# Wheel_Test_Signal.net
KiCad netlist of a schematic drawn in EAGLE
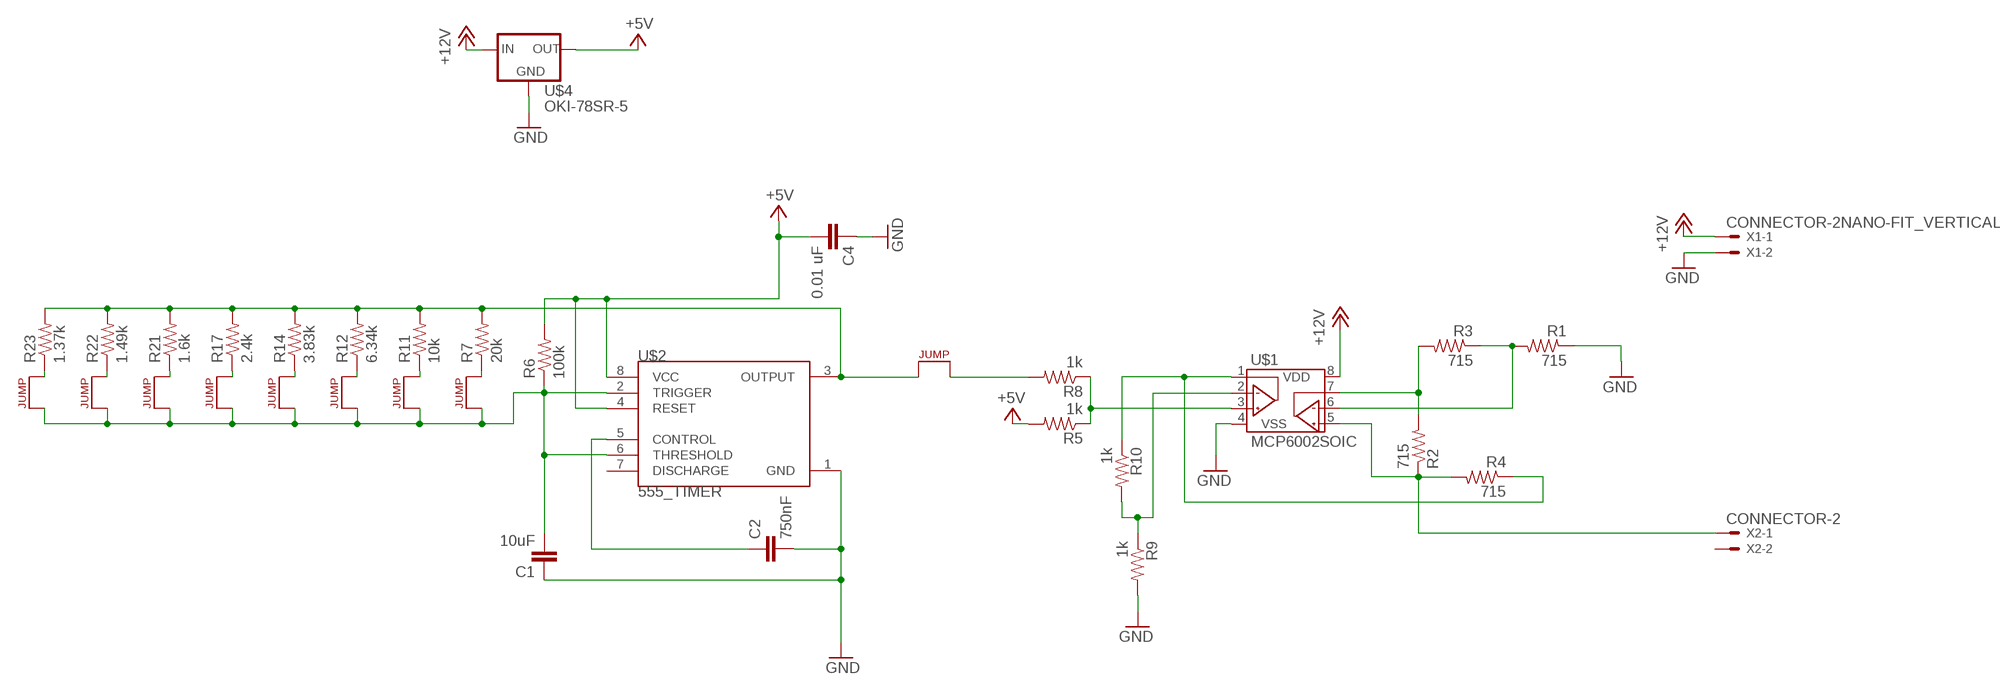
[diagram p0: schematic, sheet 1, part 1 of 2]
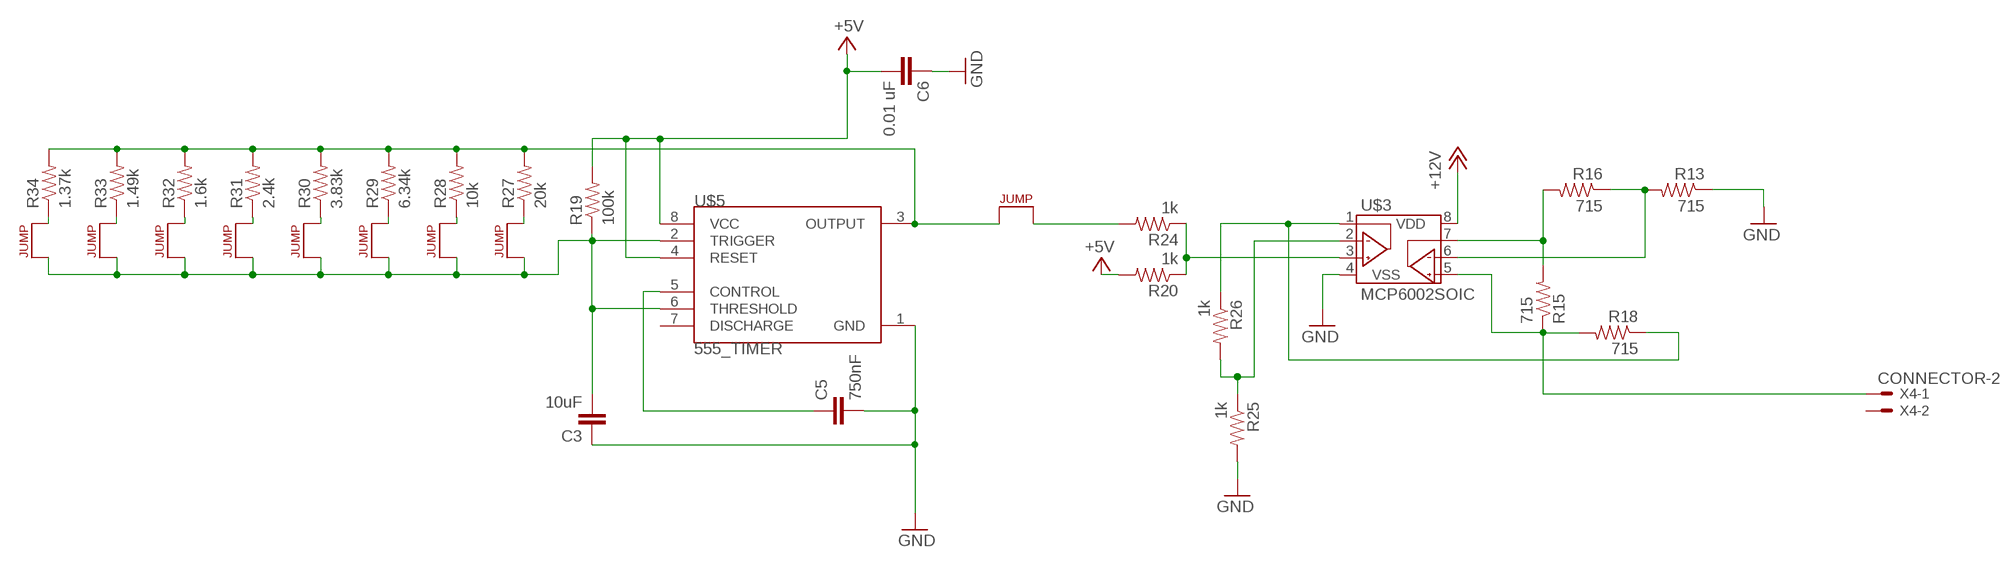
[diagram p1: schematic, sheet 1, part 2 of 2]

(export (version "E")
  (design (tool "Eeschema 10.0.6"))
  (components
    (comp (ref "C1")
      (value "10uF")
      (footprint "eagle-import:0603-CAP")
      (libsource (lib "eagle-import") (part "CAP0603-CAP"))
    )
    (comp (ref "C2")
      (value "750nF")
      (footprint "eagle-import:0603-CAP")
      (libsource (lib "eagle-import") (part "CAP0603-CAP"))
    )
    (comp (ref "C3")
      (value "10uF")
      (footprint "eagle-import:0603-CAP")
      (libsource (lib "eagle-import") (part "CAP0603-CAP"))
    )
    (comp (ref "C4")
      (value "0.01 uF")
      (footprint "eagle-import:0603-CAP")
      (libsource (lib "eagle-import") (part "CAP0603-CAP"))
    )
    (comp (ref "C5")
      (value "750nF")
      (footprint "eagle-import:0603-CAP")
      (libsource (lib "eagle-import") (part "CAP0603-CAP"))
    )
    (comp (ref "C6")
      (value "0.01 uF")
      (footprint "eagle-import:0603-CAP")
      (libsource (lib "eagle-import") (part "CAP0603-CAP"))
    )
    (comp (ref "J1")
      (value "JUMPER.1")
      (footprint "eagle-import:1X02")
      (libsource (lib "eagle-import") (part "JUMPER.1"))
    )
    (comp (ref "J2")
      (value "JUMPER.1")
      (footprint "eagle-import:1X02")
      (libsource (lib "eagle-import") (part "JUMPER.1"))
    )
    (comp (ref "J3")
      (value "JUMPER.1")
      (footprint "eagle-import:1X02")
      (libsource (lib "eagle-import") (part "JUMPER.1"))
    )
    (comp (ref "J4")
      (value "JUMPER.1")
      (footprint "eagle-import:1X02")
      (libsource (lib "eagle-import") (part "JUMPER.1"))
    )
    (comp (ref "J5")
      (value "JUMPER.1")
      (footprint "eagle-import:1X02")
      (libsource (lib "eagle-import") (part "JUMPER.1"))
    )
    (comp (ref "J6")
      (value "JUMPER.1")
      (footprint "eagle-import:1X02")
      (libsource (lib "eagle-import") (part "JUMPER.1"))
    )
    (comp (ref "J7")
      (value "JUMPER.1")
      (footprint "eagle-import:1X02")
      (libsource (lib "eagle-import") (part "JUMPER.1"))
    )
    (comp (ref "J8")
      (value "JUMPER.1")
      (footprint "eagle-import:1X02")
      (libsource (lib "eagle-import") (part "JUMPER.1"))
    )
    (comp (ref "J9")
      (value "JUMPER.1")
      (footprint "eagle-import:1X02")
      (libsource (lib "eagle-import") (part "JUMPER.1"))
    )
    (comp (ref "J10")
      (value "JUMPER.1")
      (footprint "eagle-import:1X02")
      (libsource (lib "eagle-import") (part "JUMPER.1"))
    )
    (comp (ref "J11")
      (value "JUMPER.1")
      (footprint "eagle-import:1X02")
      (libsource (lib "eagle-import") (part "JUMPER.1"))
    )
    (comp (ref "J12")
      (value "JUMPER.1")
      (footprint "eagle-import:1X02")
      (libsource (lib "eagle-import") (part "JUMPER.1"))
    )
    (comp (ref "J13")
      (value "JUMPER.1")
      (footprint "eagle-import:1X02")
      (libsource (lib "eagle-import") (part "JUMPER.1"))
    )
    (comp (ref "J14")
      (value "JUMPER.1")
      (footprint "eagle-import:1X02")
      (libsource (lib "eagle-import") (part "JUMPER.1"))
    )
    (comp (ref "J15")
      (value "JUMPER.1")
      (footprint "eagle-import:1X02")
      (libsource (lib "eagle-import") (part "JUMPER.1"))
    )
    (comp (ref "J16")
      (value "JUMPER.1")
      (footprint "eagle-import:1X02")
      (libsource (lib "eagle-import") (part "JUMPER.1"))
    )
    (comp (ref "J17")
      (value "JUMPER.1")
      (footprint "eagle-import:1X02")
      (libsource (lib "eagle-import") (part "JUMPER.1"))
    )
    (comp (ref "J18")
      (value "JUMPER.1")
      (footprint "eagle-import:1X02")
      (libsource (lib "eagle-import") (part "JUMPER.1"))
    )
    (comp (ref "R1")
      (value "715")
      (footprint "eagle-import:0603-RES")
      (libsource (lib "eagle-import") (part "RESISTOR0603"))
    )
    (comp (ref "R2")
      (value "715")
      (footprint "eagle-import:0603-RES")
      (libsource (lib "eagle-import") (part "RESISTOR0603"))
    )
    (comp (ref "R3")
      (value "715")
      (footprint "eagle-import:0603-RES")
      (libsource (lib "eagle-import") (part "RESISTOR0603"))
    )
    (comp (ref "R4")
      (value "715")
      (footprint "eagle-import:0603-RES")
      (libsource (lib "eagle-import") (part "RESISTOR0603"))
    )
    (comp (ref "R5")
      (value "1k")
      (footprint "eagle-import:0603-RES")
      (libsource (lib "eagle-import") (part "RESISTOR0603"))
    )
    (comp (ref "R6")
      (value "100k")
      (footprint "eagle-import:0603-RES")
      (libsource (lib "eagle-import") (part "RESISTOR0603"))
    )
    (comp (ref "R7")
      (value "20k")
      (footprint "eagle-import:0603-RES")
      (libsource (lib "eagle-import") (part "RESISTOR0603"))
    )
    (comp (ref "R8")
      (value "1k")
      (footprint "eagle-import:0603-RES")
      (libsource (lib "eagle-import") (part "RESISTOR0603"))
    )
    (comp (ref "R9")
      (value "1k")
      (footprint "eagle-import:0603-RES")
      (libsource (lib "eagle-import") (part "RESISTOR0603"))
    )
    (comp (ref "R10")
      (value "1k")
      (footprint "eagle-import:0603-RES")
      (libsource (lib "eagle-import") (part "RESISTOR0603"))
    )
    (comp (ref "R11")
      (value "10k")
      (footprint "eagle-import:0603-RES")
      (libsource (lib "eagle-import") (part "RESISTOR0603"))
    )
    (comp (ref "R12")
      (value "6.34k")
      (footprint "eagle-import:0603-RES")
      (libsource (lib "eagle-import") (part "RESISTOR0603"))
    )
    (comp (ref "R13")
      (value "715")
      (footprint "eagle-import:0603-RES")
      (libsource (lib "eagle-import") (part "RESISTOR0603"))
    )
    (comp (ref "R14")
      (value "3.83k")
      (footprint "eagle-import:0603-RES")
      (libsource (lib "eagle-import") (part "RESISTOR0603"))
    )
    (comp (ref "R15")
      (value "715")
      (footprint "eagle-import:0603-RES")
      (libsource (lib "eagle-import") (part "RESISTOR0603"))
    )
    (comp (ref "R16")
      (value "715")
      (footprint "eagle-import:0603-RES")
      (libsource (lib "eagle-import") (part "RESISTOR0603"))
    )
    (comp (ref "R17")
      (value "2.4k")
      (footprint "eagle-import:0603-RES")
      (libsource (lib "eagle-import") (part "RESISTOR0603"))
    )
    (comp (ref "R18")
      (value "715")
      (footprint "eagle-import:0603-RES")
      (libsource (lib "eagle-import") (part "RESISTOR0603"))
    )
    (comp (ref "R19")
      (value "100k")
      (footprint "eagle-import:0603-RES")
      (libsource (lib "eagle-import") (part "RESISTOR0603"))
    )
    (comp (ref "R20")
      (value "1k")
      (footprint "eagle-import:0603-RES")
      (libsource (lib "eagle-import") (part "RESISTOR0603"))
    )
    (comp (ref "R21")
      (value "1.6k")
      (footprint "eagle-import:0603-RES")
      (libsource (lib "eagle-import") (part "RESISTOR0603"))
    )
    (comp (ref "R22")
      (value "1.49k")
      (footprint "eagle-import:0603-RES")
      (libsource (lib "eagle-import") (part "RESISTOR0603"))
    )
    (comp (ref "R23")
      (value "1.37k")
      (footprint "eagle-import:0603-RES")
      (libsource (lib "eagle-import") (part "RESISTOR0603"))
    )
    (comp (ref "R24")
      (value "1k")
      (footprint "eagle-import:0603-RES")
      (libsource (lib "eagle-import") (part "RESISTOR0603"))
    )
    (comp (ref "R25")
      (value "1k")
      (footprint "eagle-import:0603-RES")
      (libsource (lib "eagle-import") (part "RESISTOR0603"))
    )
    (comp (ref "R26")
      (value "1k")
      (footprint "eagle-import:0603-RES")
      (libsource (lib "eagle-import") (part "RESISTOR0603"))
    )
    (comp (ref "R27")
      (value "20k")
      (footprint "eagle-import:0603-RES")
      (libsource (lib "eagle-import") (part "RESISTOR0603"))
    )
    (comp (ref "R28")
      (value "10k")
      (footprint "eagle-import:0603-RES")
      (libsource (lib "eagle-import") (part "RESISTOR0603"))
    )
    (comp (ref "R29")
      (value "6.34k")
      (footprint "eagle-import:0603-RES")
      (libsource (lib "eagle-import") (part "RESISTOR0603"))
    )
    (comp (ref "R30")
      (value "3.83k")
      (footprint "eagle-import:0603-RES")
      (libsource (lib "eagle-import") (part "RESISTOR0603"))
    )
    (comp (ref "R31")
      (value "2.4k")
      (footprint "eagle-import:0603-RES")
      (libsource (lib "eagle-import") (part "RESISTOR0603"))
    )
    (comp (ref "R32")
      (value "1.6k")
      (footprint "eagle-import:0603-RES")
      (libsource (lib "eagle-import") (part "RESISTOR0603"))
    )
    (comp (ref "R33")
      (value "1.49k")
      (footprint "eagle-import:0603-RES")
      (libsource (lib "eagle-import") (part "RESISTOR0603"))
    )
    (comp (ref "R34")
      (value "1.37k")
      (footprint "eagle-import:0603-RES")
      (libsource (lib "eagle-import") (part "RESISTOR0603"))
    )
    (comp (ref "U$1")
      (value "MCP6002SOIC")
      (footprint "eagle-import:SOIC-08")
      (libsource (lib "eagle-import") (part "MCP6002SOIC"))
    )
    (comp (ref "U$2")
      (value "555_TIMER")
      (footprint "eagle-import:DIL08")
      (libsource (lib "eagle-import") (part "555_TIMER"))
    )
    (comp (ref "U$3")
      (value "MCP6002SOIC")
      (footprint "eagle-import:SOIC-08")
      (libsource (lib "eagle-import") (part "MCP6002SOIC"))
    )
    (comp (ref "U$4")
      (value "OKI-78SR-5")
      (footprint "eagle-import:OKI-78SR")
      (libsource (lib "eagle-import") (part "OKI-78SR-5"))
    )
    (comp (ref "U$5")
      (value "555_TIMER")
      (footprint "eagle-import:DIL08")
      (libsource (lib "eagle-import") (part "555_TIMER"))
    )
    (comp (ref "X1")
      (value "CONNECTOR-2NANO-FIT_VERTICAL-2")
      (footprint "eagle-import:NANO-FIT_VERTICAL-2")
      (libsource (lib "eagle-import") (part "CONNECTOR-2NANO-FIT_VERTICAL-2"))
    )
    (comp (ref "X2")
      (value "CONNECTOR-2")
      (footprint "eagle-import:MINIFIT_5566-2")
      (libsource (lib "eagle-import") (part "CONNECTOR-2"))
    )
    (comp (ref "X4")
      (value "CONNECTOR-2")
      (footprint "eagle-import:MINIFIT_5566-2")
      (libsource (lib "eagle-import") (part "CONNECTOR-2"))
    )
  )
  (nets
    (net (code "1") (name "+5V") (class "Default")
      (node (ref "C4") (pin "2") (pinfunction "2_2") (pintype "passive"))
      (node (ref "C6") (pin "2") (pinfunction "2_2") (pintype "passive"))
      (node (ref "R19") (pin "2") (pinfunction "2_2") (pintype "passive"))
      (node (ref "R20") (pin "2") (pinfunction "2_2") (pintype "passive"))
      (node (ref "R5") (pin "2") (pinfunction "2_2") (pintype "passive"))
      (node (ref "R6") (pin "2") (pinfunction "2_2") (pintype "passive"))
      (node (ref "U$2") (pin "4") (pinfunction "RESET_4") (pintype "passive"))
      (node (ref "U$2") (pin "8") (pinfunction "VCC_8") (pintype "passive"))
      (node (ref "U$4") (pin "3") (pinfunction "OUT_3") (pintype "output"))
      (node (ref "U$5") (pin "4") (pinfunction "RESET_4") (pintype "passive"))
      (node (ref "U$5") (pin "8") (pinfunction "VCC_8") (pintype "passive"))
    )
    (net (code "2") (name "+12V") (class "Default")
      (node (ref "U$1") (pin "8") (pinfunction "VDD_8") (pintype "passive"))
      (node (ref "U$3") (pin "8") (pinfunction "VDD_8") (pintype "passive"))
      (node (ref "U$4") (pin "1") (pinfunction "IN_1") (pintype "input"))
      (node (ref "X1") (pin "P$1") (pinfunction "S_P$1") (pintype "passive"))
    )
    (net (code "3") (name "GND") (class "Default")
      (node (ref "C1") (pin "1") (pinfunction "1_1") (pintype "passive"))
      (node (ref "C2") (pin "2") (pinfunction "2_2") (pintype "passive"))
      (node (ref "C3") (pin "1") (pinfunction "1_1") (pintype "passive"))
      (node (ref "C4") (pin "1") (pinfunction "1_1") (pintype "passive"))
      (node (ref "C5") (pin "2") (pinfunction "2_2") (pintype "passive"))
      (node (ref "C6") (pin "1") (pinfunction "1_1") (pintype "passive"))
      (node (ref "R1") (pin "1") (pinfunction "1_1") (pintype "passive"))
      (node (ref "R13") (pin "1") (pinfunction "1_1") (pintype "passive"))
      (node (ref "R25") (pin "2") (pinfunction "2_2") (pintype "passive"))
      (node (ref "R9") (pin "2") (pinfunction "2_2") (pintype "passive"))
      (node (ref "U$1") (pin "4") (pinfunction "VSS_4") (pintype "passive"))
      (node (ref "U$2") (pin "1") (pinfunction "GND_1") (pintype "passive"))
      (node (ref "U$3") (pin "4") (pinfunction "VSS_4") (pintype "passive"))
      (node (ref "U$4") (pin "2") (pinfunction "GND_2") (pintype "input"))
      (node (ref "U$5") (pin "1") (pinfunction "GND_1") (pintype "passive"))
      (node (ref "X1") (pin "P$2") (pinfunction "S_P$2") (pintype "passive"))
    )
    (net (code "4") (name "Net-(J1-P$1)") (class "Default")
      (node (ref "C1") (pin "2") (pinfunction "2_2") (pintype "passive"))
      (node (ref "J1") (pin "1") (pinfunction "P$1_1") (pintype "bidirectional"))
      (node (ref "J3") (pin "1") (pinfunction "P$1_1") (pintype "bidirectional"))
      (node (ref "J4") (pin "1") (pinfunction "P$1_1") (pintype "bidirectional"))
      (node (ref "J5") (pin "1") (pinfunction "P$1_1") (pintype "bidirectional"))
      (node (ref "J6") (pin "1") (pinfunction "P$1_1") (pintype "bidirectional"))
      (node (ref "J7") (pin "1") (pinfunction "P$1_1") (pintype "bidirectional"))
      (node (ref "J8") (pin "1") (pinfunction "P$1_1") (pintype "bidirectional"))
      (node (ref "J9") (pin "1") (pinfunction "P$1_1") (pintype "bidirectional"))
      (node (ref "R6") (pin "1") (pinfunction "1_1") (pintype "passive"))
      (node (ref "U$2") (pin "2") (pinfunction "TRIGGER_2") (pintype "passive"))
      (node (ref "U$2") (pin "6") (pinfunction "THRESHOLD_6") (pintype "passive"))
    )
    (net (code "5") (name "Net-(J1-P$2)") (class "Default")
      (node (ref "J1") (pin "2") (pinfunction "P$2_2") (pintype "bidirectional"))
      (node (ref "R23") (pin "1") (pinfunction "1_1") (pintype "passive"))
    )
    (net (code "6") (name "Net-(J2-P$1)") (class "Default")
      (node (ref "J2") (pin "1") (pinfunction "P$1_1") (pintype "bidirectional"))
      (node (ref "R11") (pin "2") (pinfunction "2_2") (pintype "passive"))
      (node (ref "R12") (pin "2") (pinfunction "2_2") (pintype "passive"))
      (node (ref "R14") (pin "2") (pinfunction "2_2") (pintype "passive"))
      (node (ref "R17") (pin "2") (pinfunction "2_2") (pintype "passive"))
      (node (ref "R21") (pin "2") (pinfunction "2_2") (pintype "passive"))
      (node (ref "R22") (pin "2") (pinfunction "2_2") (pintype "passive"))
      (node (ref "R23") (pin "2") (pinfunction "2_2") (pintype "passive"))
      (node (ref "R7") (pin "2") (pinfunction "2_2") (pintype "passive"))
      (node (ref "U$2") (pin "3") (pinfunction "OUTPUT_3") (pintype "passive"))
    )
    (net (code "7") (name "Net-(J2-P$2)") (class "Default")
      (node (ref "J2") (pin "2") (pinfunction "P$2_2") (pintype "bidirectional"))
      (node (ref "R8") (pin "2") (pinfunction "2_2") (pintype "passive"))
    )
    (net (code "8") (name "Net-(J3-P$2)") (class "Default")
      (node (ref "J3") (pin "2") (pinfunction "P$2_2") (pintype "bidirectional"))
      (node (ref "R22") (pin "1") (pinfunction "1_1") (pintype "passive"))
    )
    (net (code "9") (name "Net-(J4-P$2)") (class "Default")
      (node (ref "J4") (pin "2") (pinfunction "P$2_2") (pintype "bidirectional"))
      (node (ref "R21") (pin "1") (pinfunction "1_1") (pintype "passive"))
    )
    (net (code "10") (name "Net-(J5-P$2)") (class "Default")
      (node (ref "J5") (pin "2") (pinfunction "P$2_2") (pintype "bidirectional"))
      (node (ref "R17") (pin "1") (pinfunction "1_1") (pintype "passive"))
    )
    (net (code "11") (name "Net-(J6-P$2)") (class "Default")
      (node (ref "J6") (pin "2") (pinfunction "P$2_2") (pintype "bidirectional"))
      (node (ref "R14") (pin "1") (pinfunction "1_1") (pintype "passive"))
    )
    (net (code "12") (name "Net-(J7-P$2)") (class "Default")
      (node (ref "J7") (pin "2") (pinfunction "P$2_2") (pintype "bidirectional"))
      (node (ref "R12") (pin "1") (pinfunction "1_1") (pintype "passive"))
    )
    (net (code "13") (name "Net-(J8-P$2)") (class "Default")
      (node (ref "J8") (pin "2") (pinfunction "P$2_2") (pintype "bidirectional"))
      (node (ref "R11") (pin "1") (pinfunction "1_1") (pintype "passive"))
    )
    (net (code "14") (name "Net-(J9-P$2)") (class "Default")
      (node (ref "J9") (pin "2") (pinfunction "P$2_2") (pintype "bidirectional"))
      (node (ref "R7") (pin "1") (pinfunction "1_1") (pintype "passive"))
    )
    (net (code "15") (name "Net-(J10-P$1)") (class "Default")
      (node (ref "J10") (pin "1") (pinfunction "P$1_1") (pintype "bidirectional"))
      (node (ref "R27") (pin "2") (pinfunction "2_2") (pintype "passive"))
      (node (ref "R28") (pin "2") (pinfunction "2_2") (pintype "passive"))
      (node (ref "R29") (pin "2") (pinfunction "2_2") (pintype "passive"))
      (node (ref "R30") (pin "2") (pinfunction "2_2") (pintype "passive"))
      (node (ref "R31") (pin "2") (pinfunction "2_2") (pintype "passive"))
      (node (ref "R32") (pin "2") (pinfunction "2_2") (pintype "passive"))
      (node (ref "R33") (pin "2") (pinfunction "2_2") (pintype "passive"))
      (node (ref "R34") (pin "2") (pinfunction "2_2") (pintype "passive"))
      (node (ref "U$5") (pin "3") (pinfunction "OUTPUT_3") (pintype "passive"))
    )
    (net (code "16") (name "Net-(J10-P$2)") (class "Default")
      (node (ref "J10") (pin "2") (pinfunction "P$2_2") (pintype "bidirectional"))
      (node (ref "R24") (pin "2") (pinfunction "2_2") (pintype "passive"))
    )
    (net (code "17") (name "Net-(J11-P$1)") (class "Default")
      (node (ref "C3") (pin "2") (pinfunction "2_2") (pintype "passive"))
      (node (ref "J11") (pin "1") (pinfunction "P$1_1") (pintype "bidirectional"))
      (node (ref "J12") (pin "1") (pinfunction "P$1_1") (pintype "bidirectional"))
      (node (ref "J13") (pin "1") (pinfunction "P$1_1") (pintype "bidirectional"))
      (node (ref "J14") (pin "1") (pinfunction "P$1_1") (pintype "bidirectional"))
      (node (ref "J15") (pin "1") (pinfunction "P$1_1") (pintype "bidirectional"))
      (node (ref "J16") (pin "1") (pinfunction "P$1_1") (pintype "bidirectional"))
      (node (ref "J17") (pin "1") (pinfunction "P$1_1") (pintype "bidirectional"))
      (node (ref "J18") (pin "1") (pinfunction "P$1_1") (pintype "bidirectional"))
      (node (ref "R19") (pin "1") (pinfunction "1_1") (pintype "passive"))
      (node (ref "U$5") (pin "2") (pinfunction "TRIGGER_2") (pintype "passive"))
      (node (ref "U$5") (pin "6") (pinfunction "THRESHOLD_6") (pintype "passive"))
    )
    (net (code "18") (name "Net-(J11-P$2)") (class "Default")
      (node (ref "J11") (pin "2") (pinfunction "P$2_2") (pintype "bidirectional"))
      (node (ref "R34") (pin "1") (pinfunction "1_1") (pintype "passive"))
    )
    (net (code "19") (name "Net-(J12-P$2)") (class "Default")
      (node (ref "J12") (pin "2") (pinfunction "P$2_2") (pintype "bidirectional"))
      (node (ref "R33") (pin "1") (pinfunction "1_1") (pintype "passive"))
    )
    (net (code "20") (name "Net-(J13-P$2)") (class "Default")
      (node (ref "J13") (pin "2") (pinfunction "P$2_2") (pintype "bidirectional"))
      (node (ref "R32") (pin "1") (pinfunction "1_1") (pintype "passive"))
    )
    (net (code "21") (name "Net-(J14-P$2)") (class "Default")
      (node (ref "J14") (pin "2") (pinfunction "P$2_2") (pintype "bidirectional"))
      (node (ref "R31") (pin "1") (pinfunction "1_1") (pintype "passive"))
    )
    (net (code "22") (name "Net-(J15-P$2)") (class "Default")
      (node (ref "J15") (pin "2") (pinfunction "P$2_2") (pintype "bidirectional"))
      (node (ref "R30") (pin "1") (pinfunction "1_1") (pintype "passive"))
    )
    (net (code "23") (name "Net-(J16-P$2)") (class "Default")
      (node (ref "J16") (pin "2") (pinfunction "P$2_2") (pintype "bidirectional"))
      (node (ref "R29") (pin "1") (pinfunction "1_1") (pintype "passive"))
    )
    (net (code "24") (name "Net-(J17-P$2)") (class "Default")
      (node (ref "J17") (pin "2") (pinfunction "P$2_2") (pintype "bidirectional"))
      (node (ref "R28") (pin "1") (pinfunction "1_1") (pintype "passive"))
    )
    (net (code "25") (name "Net-(J18-P$2)") (class "Default")
      (node (ref "J18") (pin "2") (pinfunction "P$2_2") (pintype "bidirectional"))
      (node (ref "R27") (pin "1") (pinfunction "1_1") (pintype "passive"))
    )
    (net (code "26") (name "Net-(U$1-VINA+)") (class "Default")
      (node (ref "R5") (pin "1") (pinfunction "1_1") (pintype "passive"))
      (node (ref "R8") (pin "1") (pinfunction "1_1") (pintype "passive"))
      (node (ref "U$1") (pin "3") (pinfunction "VINA+_3") (pintype "passive"))
    )
    (net (code "27") (name "Net-(U$1-VINA-)") (class "Default")
      (node (ref "R10") (pin "2") (pinfunction "2_2") (pintype "passive"))
      (node (ref "R9") (pin "1") (pinfunction "1_1") (pintype "passive"))
      (node (ref "U$1") (pin "2") (pinfunction "VINA-_2") (pintype "passive"))
    )
    (net (code "28") (name "Net-(U$1-VINB+)") (class "Default")
      (node (ref "R2") (pin "1") (pinfunction "1_1") (pintype "passive"))
      (node (ref "R4") (pin "2") (pinfunction "2_2") (pintype "passive"))
      (node (ref "U$1") (pin "5") (pinfunction "VINB+_5") (pintype "passive"))
      (node (ref "X2") (pin "1") (pinfunction "S_1") (pintype "passive"))
    )
    (net (code "29") (name "Net-(U$1-VINB-)") (class "Default")
      (node (ref "R1") (pin "2") (pinfunction "2_2") (pintype "passive"))
      (node (ref "R3") (pin "1") (pinfunction "1_1") (pintype "passive"))
      (node (ref "U$1") (pin "6") (pinfunction "VINB-_6") (pintype "passive"))
    )
    (net (code "30") (name "Net-(U$1-VOUTA)") (class "Default")
      (node (ref "R10") (pin "1") (pinfunction "1_1") (pintype "passive"))
      (node (ref "R4") (pin "1") (pinfunction "1_1") (pintype "passive"))
      (node (ref "U$1") (pin "1") (pinfunction "VOUTA_1") (pintype "passive"))
    )
    (net (code "31") (name "Net-(U$1-VOUTB)") (class "Default")
      (node (ref "R2") (pin "2") (pinfunction "2_2") (pintype "passive"))
      (node (ref "R3") (pin "2") (pinfunction "2_2") (pintype "passive"))
      (node (ref "U$1") (pin "7") (pinfunction "VOUTB_7") (pintype "passive"))
    )
    (net (code "32") (name "Net-(U$2-CONTROL)") (class "Default")
      (node (ref "C2") (pin "1") (pinfunction "1_1") (pintype "passive"))
      (node (ref "U$2") (pin "5") (pinfunction "CONTROL_5") (pintype "passive"))
    )
    (net (code "33") (name "Net-(U$3-VINA+)") (class "Default")
      (node (ref "R20") (pin "1") (pinfunction "1_1") (pintype "passive"))
      (node (ref "R24") (pin "1") (pinfunction "1_1") (pintype "passive"))
      (node (ref "U$3") (pin "3") (pinfunction "VINA+_3") (pintype "passive"))
    )
    (net (code "34") (name "Net-(U$3-VINA-)") (class "Default")
      (node (ref "R25") (pin "1") (pinfunction "1_1") (pintype "passive"))
      (node (ref "R26") (pin "2") (pinfunction "2_2") (pintype "passive"))
      (node (ref "U$3") (pin "2") (pinfunction "VINA-_2") (pintype "passive"))
    )
    (net (code "35") (name "Net-(U$3-VINB+)") (class "Default")
      (node (ref "R15") (pin "1") (pinfunction "1_1") (pintype "passive"))
      (node (ref "R18") (pin "2") (pinfunction "2_2") (pintype "passive"))
      (node (ref "U$3") (pin "5") (pinfunction "VINB+_5") (pintype "passive"))
      (node (ref "X4") (pin "1") (pinfunction "S_1") (pintype "passive"))
    )
    (net (code "36") (name "Net-(U$3-VINB-)") (class "Default")
      (node (ref "R13") (pin "2") (pinfunction "2_2") (pintype "passive"))
      (node (ref "R16") (pin "1") (pinfunction "1_1") (pintype "passive"))
      (node (ref "U$3") (pin "6") (pinfunction "VINB-_6") (pintype "passive"))
    )
    (net (code "37") (name "Net-(U$3-VOUTA)") (class "Default")
      (node (ref "R18") (pin "1") (pinfunction "1_1") (pintype "passive"))
      (node (ref "R26") (pin "1") (pinfunction "1_1") (pintype "passive"))
      (node (ref "U$3") (pin "1") (pinfunction "VOUTA_1") (pintype "passive"))
    )
    (net (code "38") (name "Net-(U$3-VOUTB)") (class "Default")
      (node (ref "R15") (pin "2") (pinfunction "2_2") (pintype "passive"))
      (node (ref "R16") (pin "2") (pinfunction "2_2") (pintype "passive"))
      (node (ref "U$3") (pin "7") (pinfunction "VOUTB_7") (pintype "passive"))
    )
    (net (code "39") (name "Net-(U$5-CONTROL)") (class "Default")
      (node (ref "C5") (pin "1") (pinfunction "1_1") (pintype "passive"))
      (node (ref "U$5") (pin "5") (pinfunction "CONTROL_5") (pintype "passive"))
    )
    (net (code "40") (name "unconnected-(U$2-DISCHARGE-Pad7)") (class "Default")
      (node (ref "U$2") (pin "7") (pinfunction "DISCHARGE_7") (pintype "passive"))
    )
    (net (code "41") (name "unconnected-(U$5-DISCHARGE-Pad7)") (class "Default")
      (node (ref "U$5") (pin "7") (pinfunction "DISCHARGE_7") (pintype "passive"))
    )
    (net (code "42") (name "unconnected-(X2B-S-Pad2)") (class "Default")
      (node (ref "X2") (pin "2") (pinfunction "S_2") (pintype "passive"))
    )
    (net (code "43") (name "unconnected-(X4B-S-Pad2)") (class "Default")
      (node (ref "X4") (pin "2") (pinfunction "S_2") (pintype "passive"))
    )
  )
)
